# Amphenol_ICC.net
KiCad netlist of a schematic drawn in Altium Designer
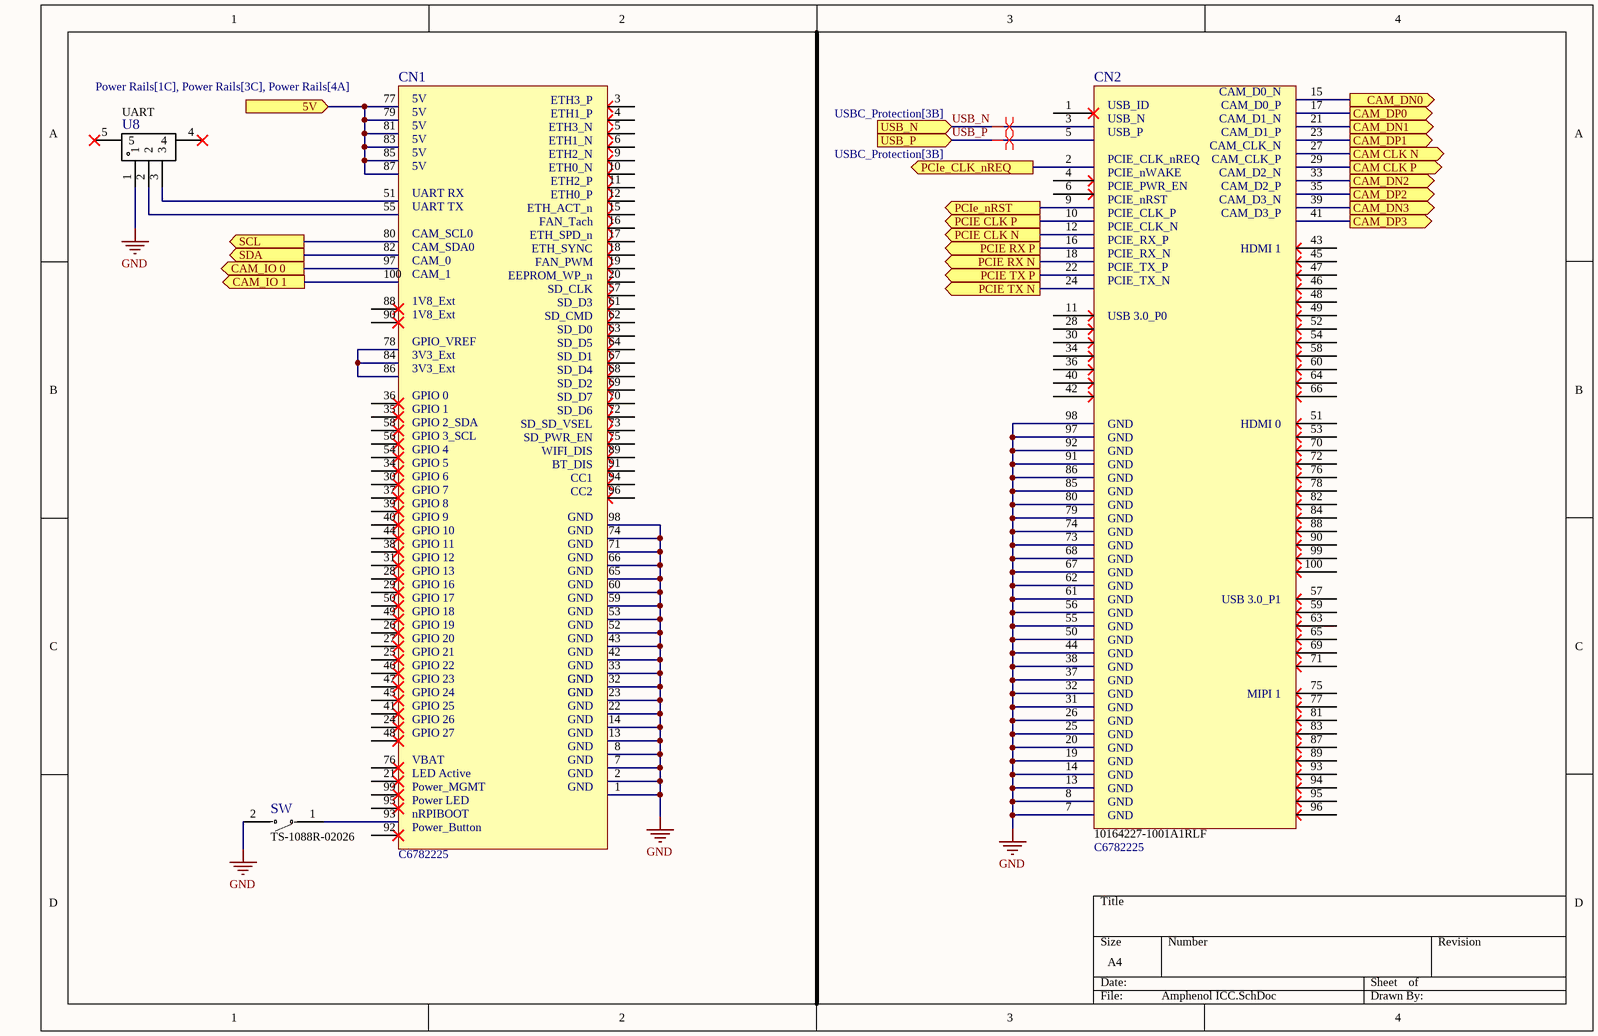
[diagram p0: Amphenol ICC.SchDoc]

(export (version "E")
  (design (tool "Eeschema 10.0.6"))
  (components
    (comp (ref "CN1")
      (value "10164227-1001A1RLF")
      (footprint "CONN-SMD_100P-P0.40_10164227-1001A1RLF")
      (description "100 Position Board to Board Connector Surface Mount,P=0.4mm Gold")
      (fields (field (name "SOURCE") "LCSC"))
      (libsource (lib "C6782225_Part 1") (part "10164227-1001A1RLF"))
    )
    (comp (ref "CN2")
      (value "10164227-1001A1RLF")
      (footprint "CONN-SMD_100P-P0.40_10164227-1001A1RLF")
      (description "100 Position Board to Board Connector Surface Mount,P=0.4mm Gold")
      (fields (field (name "NAME") "C6782225") (field (name "SOURCE") "LCSC"))
      (libsource (lib "C6782225_Part 2") (part "10164227-1001A1RLF"))
    )
    (comp (ref "SW")
      (value "TS-1088R-02026")
      (footprint "SW-SMD_L3.9-W3.0-P4.45")
      (description "Tactile Switch SPST 2mm 3.9mm x 2.93mm Surface Mount")
      (fields (field (name "SOURCE") "LCSC"))
      (libsource (lib "C455280") (part "TS-1088R-02026"))
    )
    (comp (ref "U8")
      (value "UART")
      (footprint "CONN-TH_SM03B-GHS-TB-LF-SN")
      (description "Connector Header 3 position 1.25mm Pitch 1A Surface Mount, Right Angle -25â„ƒ~+85â„ƒ")
      (fields (field (name "SOURCE") "LCSC"))
      (libsource (lib "C514175") (part "SM03B-GHS-TB_LF_SN"))
    )
  )
  (nets
    (net (code "1") (name "/5V") (class "Default")
      (node (ref "CN1") (pin "77") (pinfunction "77_77") (pintype "passive"))
      (node (ref "CN1") (pin "79") (pinfunction "79_79") (pintype "passive"))
      (node (ref "CN1") (pin "81") (pinfunction "81_81") (pintype "passive"))
      (node (ref "CN1") (pin "83") (pinfunction "83_83") (pintype "passive"))
      (node (ref "CN1") (pin "85") (pinfunction "85_85") (pintype "passive"))
      (node (ref "CN1") (pin "87") (pinfunction "87_87") (pintype "passive"))
    )
    (net (code "2") (name "/CAM CLK N") (class "Default")
      (node (ref "CN2") (pin "27") (pinfunction "MIPI_C_N_27") (pintype "passive"))
    )
    (net (code "3") (name "/CAM CLK P") (class "Default")
      (node (ref "CN2") (pin "29") (pinfunction "MIPI_C_P_29") (pintype "passive"))
    )
    (net (code "4") (name "/CAM_DN0") (class "Default")
      (node (ref "CN2") (pin "15") (pinfunction "MIPI_D0_N_15") (pintype "passive"))
    )
    (net (code "5") (name "/CAM_DN1") (class "Default")
      (node (ref "CN2") (pin "21") (pinfunction "MIPI_D1_N_21") (pintype "passive"))
    )
    (net (code "6") (name "/CAM_DN2") (class "Default")
      (node (ref "CN2") (pin "33") (pinfunction "MIPI_D2_N_33") (pintype "passive"))
    )
    (net (code "7") (name "/CAM_DN3") (class "Default")
      (node (ref "CN2") (pin "39") (pinfunction "MIPI_D3_N_39") (pintype "passive"))
    )
    (net (code "8") (name "/CAM_DP0") (class "Default")
      (node (ref "CN2") (pin "17") (pinfunction "MIPI_D0_P_17") (pintype "passive"))
    )
    (net (code "9") (name "/CAM_DP1") (class "Default")
      (node (ref "CN2") (pin "23") (pinfunction "MIPI_D1_P_23") (pintype "passive"))
    )
    (net (code "10") (name "/CAM_DP2") (class "Default")
      (node (ref "CN2") (pin "35") (pinfunction "MIPI_D2_P_35") (pintype "passive"))
    )
    (net (code "11") (name "/CAM_DP3") (class "Default")
      (node (ref "CN2") (pin "41") (pinfunction "MIPI_D3_P_41") (pintype "passive"))
    )
    (net (code "12") (name "/CAM_IO 0") (class "Default")
      (node (ref "CN1") (pin "97") (pinfunction "97_97") (pintype "passive"))
    )
    (net (code "13") (name "/CAM_IO 1") (class "Default")
      (node (ref "CN1") (pin "100") (pinfunction "100_100") (pintype "passive"))
    )
    (net (code "14") (name "/PCIE CLK N") (class "Default")
      (node (ref "CN2") (pin "12") (pinfunction "PCIe_CLK_N_12") (pintype "passive"))
    )
    (net (code "15") (name "/PCIE CLK P") (class "Default")
      (node (ref "CN2") (pin "10") (pinfunction "PCIe_CLK_P_10") (pintype "passive"))
    )
    (net (code "16") (name "/PCIE RX N") (class "Default")
      (node (ref "CN2") (pin "18") (pinfunction "PCIe_RX_N_18") (pintype "passive"))
    )
    (net (code "17") (name "/PCIE RX P") (class "Default")
      (node (ref "CN2") (pin "16") (pinfunction "PCIe_RX_P_16") (pintype "passive"))
    )
    (net (code "18") (name "/PCIE TX N") (class "Default")
      (node (ref "CN2") (pin "24") (pinfunction "PCIe_TX_N_24") (pintype "passive"))
    )
    (net (code "19") (name "/PCIE TX P") (class "Default")
      (node (ref "CN2") (pin "22") (pinfunction "PCIe_TX_P_22") (pintype "passive"))
    )
    (net (code "20") (name "/PCIe_CLK_nREQ") (class "Default")
      (node (ref "CN2") (pin "2") (pinfunction "PCIe_CLK_REQ_2") (pintype "passive"))
    )
    (net (code "21") (name "/PCIe_nRST") (class "Default")
      (node (ref "CN2") (pin "9") (pinfunction "PCIE_RST_9") (pintype "passive"))
    )
    (net (code "22") (name "/SCL") (class "Default")
      (node (ref "CN1") (pin "80") (pinfunction "80_80") (pintype "passive"))
    )
    (net (code "23") (name "/SDA") (class "Default")
      (node (ref "CN1") (pin "82") (pinfunction "82_82") (pintype "passive"))
    )
    (net (code "24") (name "/USB_N") (class "Default")
      (node (ref "CN2") (pin "3") (pinfunction "USB_N_3") (pintype "passive"))
    )
    (net (code "25") (name "/USB_P") (class "Default")
      (node (ref "CN2") (pin "5") (pinfunction "USB_P_5") (pintype "passive"))
    )
    (net (code "26") (name "GND") (class "Default")
      (node (ref "CN1") (pin "1") (pinfunction "1_1") (pintype "passive"))
      (node (ref "CN1") (pin "13") (pinfunction "13_13") (pintype "passive"))
      (node (ref "CN1") (pin "14") (pinfunction "14_14") (pintype "passive"))
      (node (ref "CN1") (pin "2") (pinfunction "2_2") (pintype "passive"))
      (node (ref "CN1") (pin "22") (pinfunction "22_22") (pintype "passive"))
      (node (ref "CN1") (pin "23") (pinfunction "23_23") (pintype "passive"))
      (node (ref "CN1") (pin "32") (pinfunction "32_32") (pintype "passive"))
      (node (ref "CN1") (pin "33") (pinfunction "33_33") (pintype "passive"))
      (node (ref "CN1") (pin "42") (pinfunction "42_42") (pintype "passive"))
      (node (ref "CN1") (pin "43") (pinfunction "43_43") (pintype "passive"))
      (node (ref "CN1") (pin "52") (pinfunction "52_52") (pintype "passive"))
      (node (ref "CN1") (pin "53") (pinfunction "53_53") (pintype "passive"))
      (node (ref "CN1") (pin "59") (pinfunction "59_59") (pintype "passive"))
      (node (ref "CN1") (pin "60") (pinfunction "60_60") (pintype "passive"))
      (node (ref "CN1") (pin "65") (pinfunction "65_65") (pintype "passive"))
      (node (ref "CN1") (pin "66") (pinfunction "66_66") (pintype "passive"))
      (node (ref "CN1") (pin "7") (pinfunction "7_7") (pintype "passive"))
      (node (ref "CN1") (pin "71") (pinfunction "71_71") (pintype "passive"))
      (node (ref "CN1") (pin "74") (pinfunction "74_74") (pintype "passive"))
      (node (ref "CN1") (pin "8") (pinfunction "8_8") (pintype "passive"))
      (node (ref "CN1") (pin "98") (pinfunction "98_98") (pintype "passive"))
      (node (ref "CN2") (pin "13") (pinfunction "GND_13") (pintype "passive"))
      (node (ref "CN2") (pin "14") (pinfunction "GND_14") (pintype "passive"))
      (node (ref "CN2") (pin "19") (pinfunction "GND_19") (pintype "passive"))
      (node (ref "CN2") (pin "20") (pinfunction "GND_20") (pintype "passive"))
      (node (ref "CN2") (pin "25") (pinfunction "GND_25") (pintype "passive"))
      (node (ref "CN2") (pin "26") (pinfunction "GND_26") (pintype "passive"))
      (node (ref "CN2") (pin "31") (pinfunction "GND_31") (pintype "passive"))
      (node (ref "CN2") (pin "32") (pinfunction "GND_32") (pintype "passive"))
      (node (ref "CN2") (pin "37") (pinfunction "GND_37") (pintype "passive"))
      (node (ref "CN2") (pin "38") (pinfunction "GND_38") (pintype "passive"))
      (node (ref "CN2") (pin "44") (pinfunction "GND_44") (pintype "passive"))
      (node (ref "CN2") (pin "50") (pinfunction "GND_50") (pintype "passive"))
      (node (ref "CN2") (pin "55") (pinfunction "GND_55") (pintype "passive"))
      (node (ref "CN2") (pin "56") (pinfunction "GND_56") (pintype "passive"))
      (node (ref "CN2") (pin "61") (pinfunction "GND_61") (pintype "passive"))
      (node (ref "CN2") (pin "62") (pinfunction "GND_62") (pintype "passive"))
      (node (ref "CN2") (pin "67") (pinfunction "GND_67") (pintype "passive"))
      (node (ref "CN2") (pin "68") (pinfunction "GND_68") (pintype "passive"))
      (node (ref "CN2") (pin "7") (pinfunction "GND_7") (pintype "passive"))
      (node (ref "CN2") (pin "73") (pinfunction "GND_73") (pintype "passive"))
      (node (ref "CN2") (pin "74") (pinfunction "GND_74") (pintype "passive"))
      (node (ref "CN2") (pin "79") (pinfunction "GND_79") (pintype "passive"))
      (node (ref "CN2") (pin "8") (pinfunction "GND_8") (pintype "passive"))
      (node (ref "CN2") (pin "80") (pinfunction "GND_80") (pintype "passive"))
      (node (ref "CN2") (pin "85") (pinfunction "GND_85") (pintype "passive"))
      (node (ref "CN2") (pin "86") (pinfunction "GND_86") (pintype "passive"))
      (node (ref "CN2") (pin "91") (pinfunction "GND_91") (pintype "passive"))
      (node (ref "CN2") (pin "92") (pinfunction "GND_92") (pintype "passive"))
      (node (ref "CN2") (pin "97") (pinfunction "GND_97") (pintype "passive"))
      (node (ref "CN2") (pin "98") (pinfunction "GND_98") (pintype "passive"))
      (node (ref "SW") (pin "2") (pinfunction "2_2") (pintype "passive"))
      (node (ref "U8") (pin "1") (pinfunction "1_1") (pintype "passive"))
    )
    (net (code "27") (name "Net-(CN1-GPIO_VREF)") (class "Default")
      (node (ref "CN1") (pin "78") (pinfunction "GPIO_VREF_78") (pintype "passive"))
      (node (ref "CN1") (pin "84") (pinfunction "84_84") (pintype "passive"))
      (node (ref "CN1") (pin "86") (pinfunction "86_86") (pintype "passive"))
    )
    (net (code "28") (name "Net-(CN1-Pad51)") (class "Default")
      (node (ref "CN1") (pin "51") (pinfunction "51_51") (pintype "passive"))
      (node (ref "U8") (pin "3") (pinfunction "3_3") (pintype "passive"))
    )
    (net (code "29") (name "Net-(CN1-Pad55)") (class "Default")
      (node (ref "CN1") (pin "55") (pinfunction "55_55") (pintype "passive"))
      (node (ref "U8") (pin "2") (pinfunction "2_2") (pintype "passive"))
    )
    (net (code "30") (name "Net-(CN1-Pad93)") (class "Default")
      (node (ref "CN1") (pin "93") (pinfunction "93_93") (pintype "passive"))
      (node (ref "SW") (pin "1") (pinfunction "1_1") (pintype "passive"))
    )
    (net (code "31") (name "unconnected-(CN1-Pad3)") (class "Default")
      (node (ref "CN1") (pin "3") (pinfunction "3_3") (pintype "passive+no_connect"))
    )
    (net (code "32") (name "unconnected-(CN1-Pad4)") (class "Default")
      (node (ref "CN1") (pin "4") (pinfunction "4_4") (pintype "passive+no_connect"))
    )
    (net (code "33") (name "unconnected-(CN1-Pad5)") (class "Default")
      (node (ref "CN1") (pin "5") (pinfunction "5_5") (pintype "passive+no_connect"))
    )
    (net (code "34") (name "unconnected-(CN1-Pad6)") (class "Default")
      (node (ref "CN1") (pin "6") (pinfunction "6_6") (pintype "passive+no_connect"))
    )
    (net (code "35") (name "unconnected-(CN1-Pad9)") (class "Default")
      (node (ref "CN1") (pin "9") (pinfunction "9_9") (pintype "passive+no_connect"))
    )
    (net (code "36") (name "unconnected-(CN1-Pad10)") (class "Default")
      (node (ref "CN1") (pin "10") (pinfunction "10_10") (pintype "passive+no_connect"))
    )
    (net (code "37") (name "unconnected-(CN1-Pad11)") (class "Default")
      (node (ref "CN1") (pin "11") (pinfunction "11_11") (pintype "passive+no_connect"))
    )
    (net (code "38") (name "unconnected-(CN1-Pad12)") (class "Default")
      (node (ref "CN1") (pin "12") (pinfunction "12_12") (pintype "passive+no_connect"))
    )
    (net (code "39") (name "unconnected-(CN1-Pad15)") (class "Default")
      (node (ref "CN1") (pin "15") (pinfunction "15_15") (pintype "passive+no_connect"))
    )
    (net (code "40") (name "unconnected-(CN1-Pad16)") (class "Default")
      (node (ref "CN1") (pin "16") (pinfunction "16_16") (pintype "passive+no_connect"))
    )
    (net (code "41") (name "unconnected-(CN1-Pad17)") (class "Default")
      (node (ref "CN1") (pin "17") (pinfunction "17_17") (pintype "passive+no_connect"))
    )
    (net (code "42") (name "unconnected-(CN1-Pad18)") (class "Default")
      (node (ref "CN1") (pin "18") (pinfunction "18_18") (pintype "passive+no_connect"))
    )
    (net (code "43") (name "unconnected-(CN1-Pad19)") (class "Default")
      (node (ref "CN1") (pin "19") (pinfunction "19_19") (pintype "passive+no_connect"))
    )
    (net (code "44") (name "unconnected-(CN1-Pad20)") (class "Default")
      (node (ref "CN1") (pin "20") (pinfunction "20_20") (pintype "passive+no_connect"))
    )
    (net (code "45") (name "unconnected-(CN1-Pad21)") (class "Default")
      (node (ref "CN1") (pin "21") (pinfunction "21_21") (pintype "passive+no_connect"))
    )
    (net (code "46") (name "unconnected-(CN1-Pad24)") (class "Default")
      (node (ref "CN1") (pin "24") (pinfunction "24_24") (pintype "passive+no_connect"))
    )
    (net (code "47") (name "unconnected-(CN1-Pad25)") (class "Default")
      (node (ref "CN1") (pin "25") (pinfunction "25_25") (pintype "passive+no_connect"))
    )
    (net (code "48") (name "unconnected-(CN1-Pad26)") (class "Default")
      (node (ref "CN1") (pin "26") (pinfunction "26_26") (pintype "passive+no_connect"))
    )
    (net (code "49") (name "unconnected-(CN1-Pad27)") (class "Default")
      (node (ref "CN1") (pin "27") (pinfunction "27_27") (pintype "passive+no_connect"))
    )
    (net (code "50") (name "unconnected-(CN1-Pad28)") (class "Default")
      (node (ref "CN1") (pin "28") (pinfunction "28_28") (pintype "passive+no_connect"))
    )
    (net (code "51") (name "unconnected-(CN1-Pad29)") (class "Default")
      (node (ref "CN1") (pin "29") (pinfunction "29_29") (pintype "passive+no_connect"))
    )
    (net (code "52") (name "unconnected-(CN1-Pad30)") (class "Default")
      (node (ref "CN1") (pin "30") (pinfunction "30_30") (pintype "passive+no_connect"))
    )
    (net (code "53") (name "unconnected-(CN1-Pad31)") (class "Default")
      (node (ref "CN1") (pin "31") (pinfunction "31_31") (pintype "passive+no_connect"))
    )
    (net (code "54") (name "unconnected-(CN1-Pad34)") (class "Default")
      (node (ref "CN1") (pin "34") (pinfunction "34_34") (pintype "passive+no_connect"))
    )
    (net (code "55") (name "unconnected-(CN1-Pad35)") (class "Default")
      (node (ref "CN1") (pin "35") (pinfunction "35_35") (pintype "passive+no_connect"))
    )
    (net (code "56") (name "unconnected-(CN1-Pad36)") (class "Default")
      (node (ref "CN1") (pin "36") (pinfunction "36_36") (pintype "passive+no_connect"))
    )
    (net (code "57") (name "unconnected-(CN1-Pad37)") (class "Default")
      (node (ref "CN1") (pin "37") (pinfunction "37_37") (pintype "passive+no_connect"))
    )
    (net (code "58") (name "unconnected-(CN1-Pad38)") (class "Default")
      (node (ref "CN1") (pin "38") (pinfunction "38_38") (pintype "passive+no_connect"))
    )
    (net (code "59") (name "unconnected-(CN1-Pad39)") (class "Default")
      (node (ref "CN1") (pin "39") (pinfunction "39_39") (pintype "passive+no_connect"))
    )
    (net (code "60") (name "unconnected-(CN1-Pad40)") (class "Default")
      (node (ref "CN1") (pin "40") (pinfunction "40_40") (pintype "passive+no_connect"))
    )
    (net (code "61") (name "unconnected-(CN1-Pad41)") (class "Default")
      (node (ref "CN1") (pin "41") (pinfunction "41_41") (pintype "passive+no_connect"))
    )
    (net (code "62") (name "unconnected-(CN1-Pad44)") (class "Default")
      (node (ref "CN1") (pin "44") (pinfunction "44_44") (pintype "passive+no_connect"))
    )
    (net (code "63") (name "unconnected-(CN1-Pad45)") (class "Default")
      (node (ref "CN1") (pin "45") (pinfunction "45_45") (pintype "passive+no_connect"))
    )
    (net (code "64") (name "unconnected-(CN1-Pad46)") (class "Default")
      (node (ref "CN1") (pin "46") (pinfunction "46_46") (pintype "passive+no_connect"))
    )
    (net (code "65") (name "unconnected-(CN1-Pad47)") (class "Default")
      (node (ref "CN1") (pin "47") (pinfunction "47_47") (pintype "passive+no_connect"))
    )
    (net (code "66") (name "unconnected-(CN1-Pad48)") (class "Default")
      (node (ref "CN1") (pin "48") (pinfunction "48_48") (pintype "passive+no_connect"))
    )
    (net (code "67") (name "unconnected-(CN1-Pad49)") (class "Default")
      (node (ref "CN1") (pin "49") (pinfunction "49_49") (pintype "passive+no_connect"))
    )
    (net (code "68") (name "unconnected-(CN1-Pad50)") (class "Default")
      (node (ref "CN1") (pin "50") (pinfunction "50_50") (pintype "passive+no_connect"))
    )
    (net (code "69") (name "unconnected-(CN1-Pad54)") (class "Default")
      (node (ref "CN1") (pin "54") (pinfunction "54_54") (pintype "passive+no_connect"))
    )
    (net (code "70") (name "unconnected-(CN1-Pad56)") (class "Default")
      (node (ref "CN1") (pin "56") (pinfunction "56_56") (pintype "passive+no_connect"))
    )
    (net (code "71") (name "unconnected-(CN1-Pad57)") (class "Default")
      (node (ref "CN1") (pin "57") (pinfunction "57_57") (pintype "passive+no_connect"))
    )
    (net (code "72") (name "unconnected-(CN1-Pad58)") (class "Default")
      (node (ref "CN1") (pin "58") (pinfunction "58_58") (pintype "passive+no_connect"))
    )
    (net (code "73") (name "unconnected-(CN1-Pad61)") (class "Default")
      (node (ref "CN1") (pin "61") (pinfunction "61_61") (pintype "passive+no_connect"))
    )
    (net (code "74") (name "unconnected-(CN1-Pad62)") (class "Default")
      (node (ref "CN1") (pin "62") (pinfunction "62_62") (pintype "passive+no_connect"))
    )
    (net (code "75") (name "unconnected-(CN1-Pad63)") (class "Default")
      (node (ref "CN1") (pin "63") (pinfunction "63_63") (pintype "passive+no_connect"))
    )
    (net (code "76") (name "unconnected-(CN1-Pad64)") (class "Default")
      (node (ref "CN1") (pin "64") (pinfunction "64_64") (pintype "passive+no_connect"))
    )
    (net (code "77") (name "unconnected-(CN1-Pad67)") (class "Default")
      (node (ref "CN1") (pin "67") (pinfunction "67_67") (pintype "passive+no_connect"))
    )
    (net (code "78") (name "unconnected-(CN1-Pad68)") (class "Default")
      (node (ref "CN1") (pin "68") (pinfunction "68_68") (pintype "passive+no_connect"))
    )
    (net (code "79") (name "unconnected-(CN1-Pad69)") (class "Default")
      (node (ref "CN1") (pin "69") (pinfunction "69_69") (pintype "passive+no_connect"))
    )
    (net (code "80") (name "unconnected-(CN1-Pad70)") (class "Default")
      (node (ref "CN1") (pin "70") (pinfunction "70_70") (pintype "passive+no_connect"))
    )
    (net (code "81") (name "unconnected-(CN1-Pad72)") (class "Default")
      (node (ref "CN1") (pin "72") (pinfunction "72_72") (pintype "passive+no_connect"))
    )
    (net (code "82") (name "unconnected-(CN1-Pad73)") (class "Default")
      (node (ref "CN1") (pin "73") (pinfunction "73_73") (pintype "passive+no_connect"))
    )
    (net (code "83") (name "unconnected-(CN1-Pad75)") (class "Default")
      (node (ref "CN1") (pin "75") (pinfunction "75_75") (pintype "passive+no_connect"))
    )
    (net (code "84") (name "unconnected-(CN1-Pad76)") (class "Default")
      (node (ref "CN1") (pin "76") (pinfunction "76_76") (pintype "passive+no_connect"))
    )
    (net (code "85") (name "unconnected-(CN1-Pad88)") (class "Default")
      (node (ref "CN1") (pin "88") (pinfunction "88_88") (pintype "passive+no_connect"))
    )
    (net (code "86") (name "unconnected-(CN1-Pad89)") (class "Default")
      (node (ref "CN1") (pin "89") (pinfunction "89_89") (pintype "passive+no_connect"))
    )
    (net (code "87") (name "unconnected-(CN1-Pad90)") (class "Default")
      (node (ref "CN1") (pin "90") (pinfunction "90_90") (pintype "passive+no_connect"))
    )
    (net (code "88") (name "unconnected-(CN1-Pad91)") (class "Default")
      (node (ref "CN1") (pin "91") (pinfunction "91_91") (pintype "passive+no_connect"))
    )
    (net (code "89") (name "unconnected-(CN1-Pad92)") (class "Default")
      (node (ref "CN1") (pin "92") (pinfunction "92_92") (pintype "passive+no_connect"))
    )
    (net (code "90") (name "unconnected-(CN1-Pad94)") (class "Default")
      (node (ref "CN1") (pin "94") (pinfunction "94_94") (pintype "passive+no_connect"))
    )
    (net (code "91") (name "unconnected-(CN1-Pad95)") (class "Default")
      (node (ref "CN1") (pin "95") (pinfunction "95_95") (pintype "passive+no_connect"))
    )
    (net (code "92") (name "unconnected-(CN1-Pad96)") (class "Default")
      (node (ref "CN1") (pin "96") (pinfunction "96_96") (pintype "passive+no_connect"))
    )
    (net (code "93") (name "unconnected-(CN1-Pad99)") (class "Default")
      (node (ref "CN1") (pin "99") (pinfunction "99_99") (pintype "passive+no_connect"))
    )
    (net (code "94") (name "unconnected-(CN2-111-Pad11)") (class "Default")
      (node (ref "CN2") (pin "11") (pinfunction "111_11") (pintype "passive+no_connect"))
    )
    (net (code "95") (name "unconnected-(CN2-128-Pad28)") (class "Default")
      (node (ref "CN2") (pin "28") (pinfunction "128_28") (pintype "passive+no_connect"))
    )
    (net (code "96") (name "unconnected-(CN2-130-Pad30)") (class "Default")
      (node (ref "CN2") (pin "30") (pinfunction "130_30") (pintype "passive+no_connect"))
    )
    (net (code "97") (name "unconnected-(CN2-134-Pad34)") (class "Default")
      (node (ref "CN2") (pin "34") (pinfunction "134_34") (pintype "passive+no_connect"))
    )
    (net (code "98") (name "unconnected-(CN2-136-Pad36)") (class "Default")
      (node (ref "CN2") (pin "36") (pinfunction "136_36") (pintype "passive+no_connect"))
    )
    (net (code "99") (name "unconnected-(CN2-140-Pad40)") (class "Default")
      (node (ref "CN2") (pin "40") (pinfunction "140_40") (pintype "passive+no_connect"))
    )
    (net (code "100") (name "unconnected-(CN2-142-Pad42)") (class "Default")
      (node (ref "CN2") (pin "42") (pinfunction "142_42") (pintype "passive+no_connect"))
    )
    (net (code "101") (name "unconnected-(CN2-143-Pad43)") (class "Default")
      (node (ref "CN2") (pin "43") (pinfunction "143_43") (pintype "passive+no_connect"))
    )
    (net (code "102") (name "unconnected-(CN2-145-Pad45)") (class "Default")
      (node (ref "CN2") (pin "45") (pinfunction "145_45") (pintype "passive+no_connect"))
    )
    (net (code "103") (name "unconnected-(CN2-146-Pad46)") (class "Default")
      (node (ref "CN2") (pin "46") (pinfunction "146_46") (pintype "passive+no_connect"))
    )
    (net (code "104") (name "unconnected-(CN2-147-Pad47)") (class "Default")
      (node (ref "CN2") (pin "47") (pinfunction "147_47") (pintype "passive+no_connect"))
    )
    (net (code "105") (name "unconnected-(CN2-148-Pad48)") (class "Default")
      (node (ref "CN2") (pin "48") (pinfunction "148_48") (pintype "passive+no_connect"))
    )
    (net (code "106") (name "unconnected-(CN2-149-Pad49)") (class "Default")
      (node (ref "CN2") (pin "49") (pinfunction "149_49") (pintype "passive+no_connect"))
    )
    (net (code "107") (name "unconnected-(CN2-151-Pad51)") (class "Default")
      (node (ref "CN2") (pin "51") (pinfunction "151_51") (pintype "passive+no_connect"))
    )
    (net (code "108") (name "unconnected-(CN2-152-Pad52)") (class "Default")
      (node (ref "CN2") (pin "52") (pinfunction "152_52") (pintype "passive+no_connect"))
    )
    (net (code "109") (name "unconnected-(CN2-153-Pad53)") (class "Default")
      (node (ref "CN2") (pin "53") (pinfunction "153_53") (pintype "passive+no_connect"))
    )
    (net (code "110") (name "unconnected-(CN2-154-Pad54)") (class "Default")
      (node (ref "CN2") (pin "54") (pinfunction "154_54") (pintype "passive+no_connect"))
    )
    (net (code "111") (name "unconnected-(CN2-157-Pad57)") (class "Default")
      (node (ref "CN2") (pin "57") (pinfunction "157_57") (pintype "passive+no_connect"))
    )
    (net (code "112") (name "unconnected-(CN2-158-Pad58)") (class "Default")
      (node (ref "CN2") (pin "58") (pinfunction "158_58") (pintype "passive+no_connect"))
    )
    (net (code "113") (name "unconnected-(CN2-159-Pad59)") (class "Default")
      (node (ref "CN2") (pin "59") (pinfunction "159_59") (pintype "passive+no_connect"))
    )
    (net (code "114") (name "unconnected-(CN2-160-Pad60)") (class "Default")
      (node (ref "CN2") (pin "60") (pinfunction "160_60") (pintype "passive+no_connect"))
    )
    (net (code "115") (name "unconnected-(CN2-163-Pad63)") (class "Default")
      (node (ref "CN2") (pin "63") (pinfunction "163_63") (pintype "passive+no_connect"))
    )
    (net (code "116") (name "unconnected-(CN2-164-Pad64)") (class "Default")
      (node (ref "CN2") (pin "64") (pinfunction "164_64") (pintype "passive+no_connect"))
    )
    (net (code "117") (name "unconnected-(CN2-165-Pad65)") (class "Default")
      (node (ref "CN2") (pin "65") (pinfunction "165_65") (pintype "passive+no_connect"))
    )
    (net (code "118") (name "unconnected-(CN2-166-Pad66)") (class "Default")
      (node (ref "CN2") (pin "66") (pinfunction "166_66") (pintype "passive+no_connect"))
    )
    (net (code "119") (name "unconnected-(CN2-169-Pad69)") (class "Default")
      (node (ref "CN2") (pin "69") (pinfunction "169_69") (pintype "passive+no_connect"))
    )
    (net (code "120") (name "unconnected-(CN2-170-Pad70)") (class "Default")
      (node (ref "CN2") (pin "70") (pinfunction "170_70") (pintype "passive+no_connect"))
    )
    (net (code "121") (name "unconnected-(CN2-171-Pad71)") (class "Default")
      (node (ref "CN2") (pin "71") (pinfunction "171_71") (pintype "passive+no_connect"))
    )
    (net (code "122") (name "unconnected-(CN2-172-Pad72)") (class "Default")
      (node (ref "CN2") (pin "72") (pinfunction "172_72") (pintype "passive+no_connect"))
    )
    (net (code "123") (name "unconnected-(CN2-175-Pad75)") (class "Default")
      (node (ref "CN2") (pin "75") (pinfunction "175_75") (pintype "passive+no_connect"))
    )
    (net (code "124") (name "unconnected-(CN2-176-Pad76)") (class "Default")
      (node (ref "CN2") (pin "76") (pinfunction "176_76") (pintype "passive+no_connect"))
    )
    (net (code "125") (name "unconnected-(CN2-177-Pad77)") (class "Default")
      (node (ref "CN2") (pin "77") (pinfunction "177_77") (pintype "passive+no_connect"))
    )
    (net (code "126") (name "unconnected-(CN2-178-Pad78)") (class "Default")
      (node (ref "CN2") (pin "78") (pinfunction "178_78") (pintype "passive+no_connect"))
    )
    (net (code "127") (name "unconnected-(CN2-181-Pad81)") (class "Default")
      (node (ref "CN2") (pin "81") (pinfunction "181_81") (pintype "passive+no_connect"))
    )
    (net (code "128") (name "unconnected-(CN2-182-Pad82)") (class "Default")
      (node (ref "CN2") (pin "82") (pinfunction "182_82") (pintype "passive+no_connect"))
    )
    (net (code "129") (name "unconnected-(CN2-183-Pad83)") (class "Default")
      (node (ref "CN2") (pin "83") (pinfunction "183_83") (pintype "passive+no_connect"))
    )
    (net (code "130") (name "unconnected-(CN2-184-Pad84)") (class "Default")
      (node (ref "CN2") (pin "84") (pinfunction "184_84") (pintype "passive+no_connect"))
    )
    (net (code "131") (name "unconnected-(CN2-187-Pad87)") (class "Default")
      (node (ref "CN2") (pin "87") (pinfunction "187_87") (pintype "passive+no_connect"))
    )
    (net (code "132") (name "unconnected-(CN2-188-Pad88)") (class "Default")
      (node (ref "CN2") (pin "88") (pinfunction "188_88") (pintype "passive+no_connect"))
    )
    (net (code "133") (name "unconnected-(CN2-189-Pad89)") (class "Default")
      (node (ref "CN2") (pin "89") (pinfunction "189_89") (pintype "passive+no_connect"))
    )
    (net (code "134") (name "unconnected-(CN2-190-Pad90)") (class "Default")
      (node (ref "CN2") (pin "90") (pinfunction "190_90") (pintype "passive+no_connect"))
    )
    (net (code "135") (name "unconnected-(CN2-193-Pad93)") (class "Default")
      (node (ref "CN2") (pin "93") (pinfunction "193_93") (pintype "passive+no_connect"))
    )
    (net (code "136") (name "unconnected-(CN2-194-Pad94)") (class "Default")
      (node (ref "CN2") (pin "94") (pinfunction "194_94") (pintype "passive+no_connect"))
    )
    (net (code "137") (name "unconnected-(CN2-195-Pad95)") (class "Default")
      (node (ref "CN2") (pin "95") (pinfunction "195_95") (pintype "passive+no_connect"))
    )
    (net (code "138") (name "unconnected-(CN2-196-Pad96)") (class "Default")
      (node (ref "CN2") (pin "96") (pinfunction "196_96") (pintype "passive+no_connect"))
    )
    (net (code "139") (name "unconnected-(CN2-199-Pad99)") (class "Default")
      (node (ref "CN2") (pin "99") (pinfunction "199_99") (pintype "passive+no_connect"))
    )
    (net (code "140") (name "unconnected-(CN2-200-Pad100)") (class "Default")
      (node (ref "CN2") (pin "100") (pinfunction "200_100") (pintype "passive+no_connect"))
    )
    (net (code "141") (name "unconnected-(CN2-PCIE_PWR_EN-Pad6)") (class "Default")
      (node (ref "CN2") (pin "6") (pinfunction "PCIE_PWR_EN_6") (pintype "passive+no_connect"))
    )
    (net (code "142") (name "unconnected-(CN2-PCIe_WAKE-Pad4)") (class "Default")
      (node (ref "CN2") (pin "4") (pinfunction "PCIe_WAKE_4") (pintype "passive+no_connect"))
    )
    (net (code "143") (name "unconnected-(CN2-USB_ID-Pad1)") (class "Default")
      (node (ref "CN2") (pin "1") (pinfunction "USB_ID_1") (pintype "passive+no_connect"))
    )
    (net (code "144") (name "unconnected-(U8-Pad4)") (class "Default")
      (node (ref "U8") (pin "4") (pinfunction "4_4") (pintype "passive+no_connect"))
    )
    (net (code "145") (name "unconnected-(U8-Pad5)") (class "Default")
      (node (ref "U8") (pin "5") (pinfunction "5_5") (pintype "passive+no_connect"))
    )
  )
)
